# coil_inj_drivers.net
KiCad netlist of a schematic drawn in Altium Designer
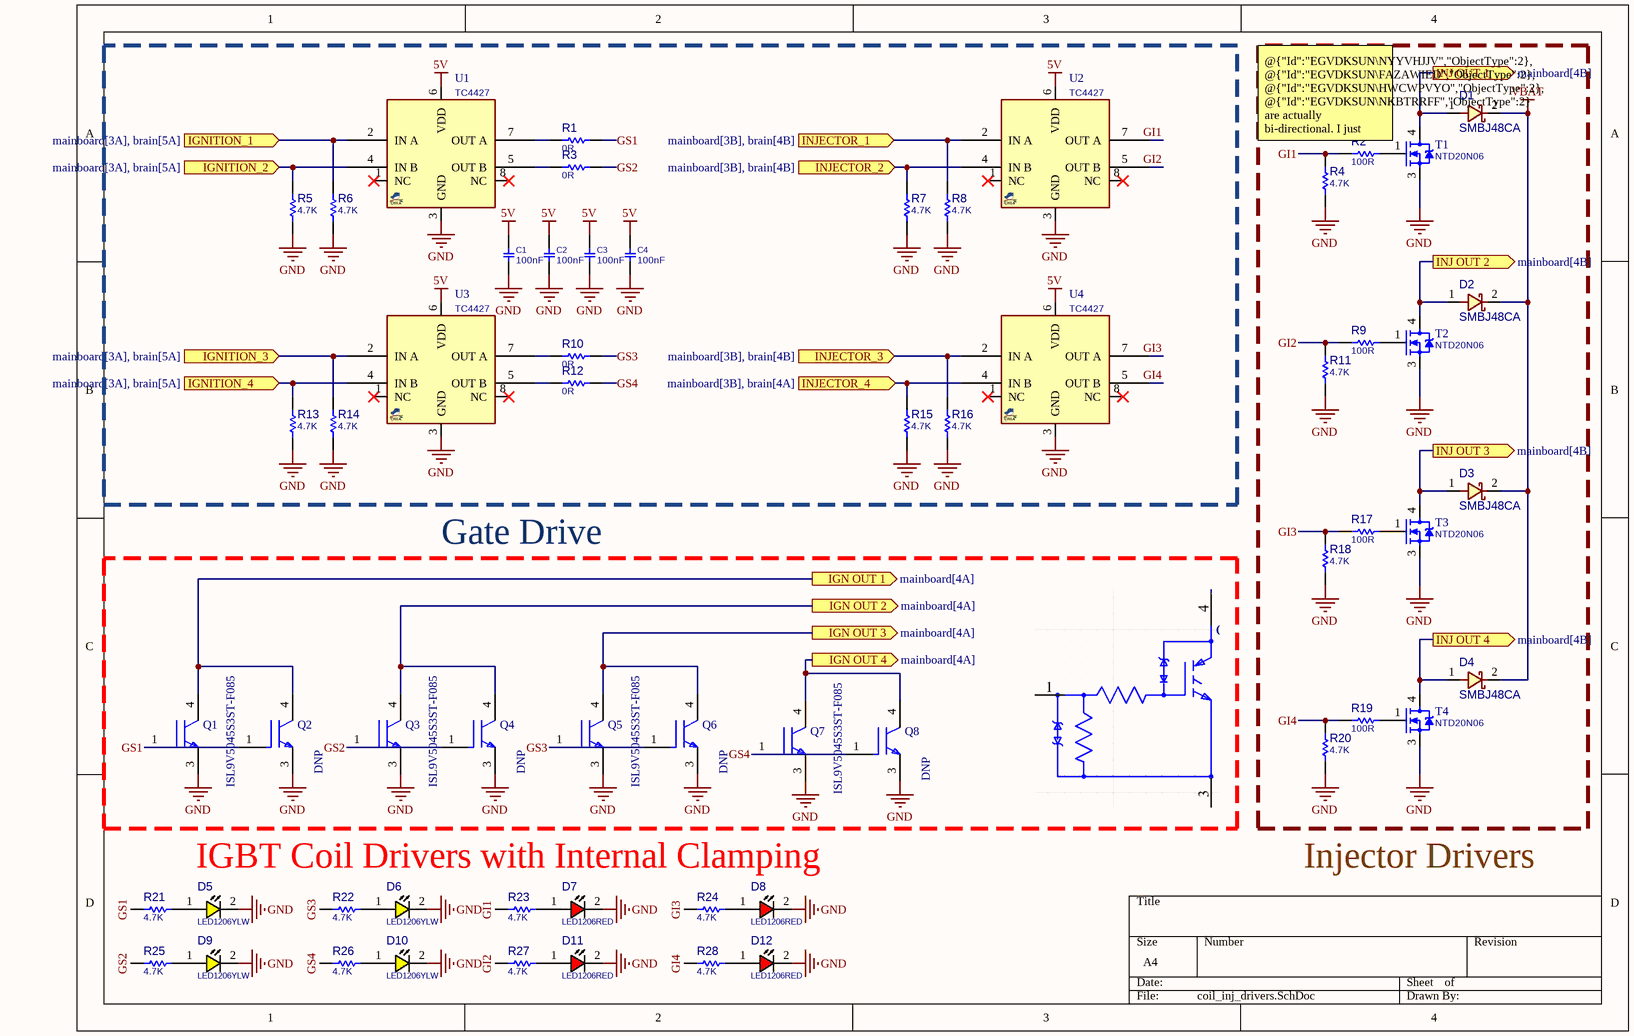
[diagram p0: coil_inj_drivers.SchDoc]

(export (version "E")
  (design (tool "Eeschema 10.0.6"))
  (components
    (comp (ref "C1")
      (value "100nF")
      (footprint "C1206")
      (description "CAP, MLCC")
      (fields (field (name "MANF_P#") "MANF_PART#") (field (name "MANF") "Murata"))
      (libsource (lib "passive_smd") (part "CAP_SMD_MLCC"))
    )
    (comp (ref "C2")
      (value "100nF")
      (footprint "C1206")
      (description "CAP, MLCC")
      (fields (field (name "MANF_P#") "MANF_PART#") (field (name "MANF") "Murata"))
      (libsource (lib "passive_smd") (part "CAP_SMD_MLCC"))
    )
    (comp (ref "C3")
      (value "100nF")
      (footprint "C1206")
      (description "CAP, MLCC")
      (fields (field (name "MANF_P#") "MANF_PART#") (field (name "MANF") "Murata"))
      (libsource (lib "passive_smd") (part "CAP_SMD_MLCC"))
    )
    (comp (ref "C4")
      (value "100nF")
      (footprint "C1206")
      (description "CAP, MLCC")
      (fields (field (name "MANF_P#") "MANF_PART#") (field (name "MANF") "Murata"))
      (libsource (lib "passive_smd") (part "CAP_SMD_MLCC"))
    )
    (comp (ref "D1")
      (value "SMBJ48CA")
      (footprint "D_SMB")
      (description "DIODE, SCHOTTKY, 20V, 3A")
      (fields (field (name "MANF") "VISHAY") (field (name "MANF_P#") "SS34"))
      (libsource (lib "diode") (part "DIODE_SMD_SCHOTTKY_SS34"))
    )
    (comp (ref "D2")
      (value "SMBJ48CA")
      (footprint "D_SMB")
      (description "DIODE, SCHOTTKY, 20V, 3A")
      (fields (field (name "MANF") "VISHAY") (field (name "MANF_P#") "SS34"))
      (libsource (lib "diode") (part "DIODE_SMD_SCHOTTKY_SS34"))
    )
    (comp (ref "D3")
      (value "SMBJ48CA")
      (footprint "D_SMB")
      (description "DIODE, SCHOTTKY, 20V, 3A")
      (fields (field (name "MANF") "VISHAY") (field (name "MANF_P#") "SS34"))
      (libsource (lib "diode") (part "DIODE_SMD_SCHOTTKY_SS34"))
    )
    (comp (ref "D4")
      (value "SMBJ48CA")
      (footprint "D_SMB")
      (description "DIODE, SCHOTTKY, 20V, 3A")
      (fields (field (name "MANF") "VISHAY") (field (name "MANF_P#") "SS34"))
      (libsource (lib "diode") (part "DIODE_SMD_SCHOTTKY_SS34"))
    )
    (comp (ref "D5")
      (value "LED1206YLW")
      (footprint "LED1206YLW")
      (description "LED, SMD, 1206, YELLOW")
      (fields (field (name "MANF") "MANF") (field (name "MANF_P#") "MANF_PART#"))
      (libsource (lib "led(diode)") (part "LED_SMD_1206_YLW"))
    )
    (comp (ref "D6")
      (value "LED1206YLW")
      (footprint "LED1206YLW")
      (description "LED, SMD, 1206, YELLOW")
      (fields (field (name "MANF") "MANF") (field (name "MANF_P#") "MANF_PART#"))
      (libsource (lib "led(diode)") (part "LED_SMD_1206_YLW"))
    )
    (comp (ref "D7")
      (value "LED1206RED")
      (footprint "LED1206RED")
      (description "LED, SMD, 1206, RED")
      (fields (field (name "MANF") "MANF") (field (name "MANF_P#") "MANF_PART#"))
      (libsource (lib "led(diode)") (part "LED_SMD_1206_RED"))
    )
    (comp (ref "D8")
      (value "LED1206RED")
      (footprint "LED1206RED")
      (description "LED, SMD, 1206, RED")
      (fields (field (name "MANF") "MANF") (field (name "MANF_P#") "MANF_PART#"))
      (libsource (lib "led(diode)") (part "LED_SMD_1206_RED"))
    )
    (comp (ref "D9")
      (value "LED1206YLW")
      (footprint "LED1206YLW")
      (description "LED, SMD, 1206, YELLOW")
      (fields (field (name "MANF") "MANF") (field (name "MANF_P#") "MANF_PART#"))
      (libsource (lib "led(diode)") (part "LED_SMD_1206_YLW"))
    )
    (comp (ref "D10")
      (value "LED1206YLW")
      (footprint "LED1206YLW")
      (description "LED, SMD, 1206, YELLOW")
      (fields (field (name "MANF") "MANF") (field (name "MANF_P#") "MANF_PART#"))
      (libsource (lib "led(diode)") (part "LED_SMD_1206_YLW"))
    )
    (comp (ref "D11")
      (value "LED1206RED")
      (footprint "LED1206RED")
      (description "LED, SMD, 1206, RED")
      (fields (field (name "MANF") "MANF") (field (name "MANF_P#") "MANF_PART#"))
      (libsource (lib "led(diode)") (part "LED_SMD_1206_RED"))
    )
    (comp (ref "D12")
      (value "LED1206RED")
      (footprint "LED1206RED")
      (description "LED, SMD, 1206, RED")
      (fields (field (name "MANF") "MANF") (field (name "MANF_P#") "MANF_PART#"))
      (libsource (lib "led(diode)") (part "LED_SMD_1206_RED"))
    )
    (comp (ref "Q1")
      (value "ISL9V5045S3ST-F085")
      (footprint "FP-418AJ-MFG")
      (description "ISL9V5045S3ST-F085 Trans IGBT Chip N-CH 445V 51A 300000mW Automotive 3-Pin(2+Tab) D2PAK T/R")
      (libsource (lib "Altium Content Vault") (part "6c8866ed3e1cdd60f937be2a65c5a66"))
    )
    (comp (ref "Q2")
      (value "DNP")
      (footprint "FP-369AS-MFG")
      (description "IGNITION IGBT")
      (libsource (lib "alib") (part "IGNITION IGBT"))
    )
    (comp (ref "Q3")
      (value "ISL9V5045S3ST-F085")
      (footprint "FP-418AJ-MFG")
      (description "ISL9V5045S3ST-F085 Trans IGBT Chip N-CH 445V 51A 300000mW Automotive 3-Pin(2+Tab) D2PAK T/R")
      (libsource (lib "Altium Content Vault") (part "6c8866ed3e1cdd60f937be2a65c5a66"))
    )
    (comp (ref "Q4")
      (value "DNP")
      (footprint "FP-369AS-MFG")
      (description "IGNITION IGBT")
      (libsource (lib "alib") (part "IGNITION IGBT"))
    )
    (comp (ref "Q5")
      (value "ISL9V5045S3ST-F085")
      (footprint "FP-418AJ-MFG")
      (description "ISL9V5045S3ST-F085 Trans IGBT Chip N-CH 445V 51A 300000mW Automotive 3-Pin(2+Tab) D2PAK T/R")
      (libsource (lib "Altium Content Vault") (part "6c8866ed3e1cdd60f937be2a65c5a66"))
    )
    (comp (ref "Q6")
      (value "DNP")
      (footprint "FP-369AS-MFG")
      (description "IGNITION IGBT")
      (libsource (lib "alib") (part "IGNITION IGBT"))
    )
    (comp (ref "Q7")
      (value "ISL9V5045S3ST-F085")
      (footprint "FP-418AJ-MFG")
      (description "ISL9V5045S3ST-F085 Trans IGBT Chip N-CH 445V 51A 300000mW Automotive 3-Pin(2+Tab) D2PAK T/R")
      (libsource (lib "Altium Content Vault") (part "6c8866ed3e1cdd60f937be2a65c5a66"))
    )
    (comp (ref "Q8")
      (value "DNP")
      (footprint "FP-369AS-MFG")
      (description "IGNITION IGBT")
      (libsource (lib "alib") (part "IGNITION IGBT"))
    )
    (comp (ref "R1")
      (value "0R")
      (footprint "R0805")
      (description "RESISTOR, SMD")
      (libsource (lib "passive_smd") (part "RES_SMD_0805"))
    )
    (comp (ref "R2")
      (value "100R")
      (footprint "R0805")
      (description "RESISTOR, SMD")
      (libsource (lib "passive_smd") (part "RES_SMD_0805"))
    )
    (comp (ref "R3")
      (value "0R")
      (footprint "R0805")
      (description "RESISTOR, SMD")
      (libsource (lib "passive_smd") (part "RES_SMD_0805"))
    )
    (comp (ref "R4")
      (value "4.7K")
      (footprint "R0805")
      (description "RESISTOR, SMD")
      (libsource (lib "passive_smd") (part "RES_SMD_0805"))
    )
    (comp (ref "R5")
      (value "4.7K")
      (footprint "R0805")
      (description "RESISTOR, SMD")
      (libsource (lib "passive_smd") (part "RES_SMD_0805"))
    )
    (comp (ref "R6")
      (value "4.7K")
      (footprint "R0805")
      (description "RESISTOR, SMD")
      (libsource (lib "passive_smd") (part "RES_SMD_0805"))
    )
    (comp (ref "R7")
      (value "4.7K")
      (footprint "R0805")
      (description "RESISTOR, SMD")
      (libsource (lib "passive_smd") (part "RES_SMD_0805"))
    )
    (comp (ref "R8")
      (value "4.7K")
      (footprint "R0805")
      (description "RESISTOR, SMD")
      (libsource (lib "passive_smd") (part "RES_SMD_0805"))
    )
    (comp (ref "R9")
      (value "100R")
      (footprint "R0805")
      (description "RESISTOR, SMD")
      (libsource (lib "passive_smd") (part "RES_SMD_0805"))
    )
    (comp (ref "R10")
      (value "0R")
      (footprint "R0805")
      (description "RESISTOR, SMD")
      (libsource (lib "passive_smd") (part "RES_SMD_0805"))
    )
    (comp (ref "R11")
      (value "4.7K")
      (footprint "R0805")
      (description "RESISTOR, SMD")
      (libsource (lib "passive_smd") (part "RES_SMD_0805"))
    )
    (comp (ref "R12")
      (value "0R")
      (footprint "R0805")
      (description "RESISTOR, SMD")
      (libsource (lib "passive_smd") (part "RES_SMD_0805"))
    )
    (comp (ref "R13")
      (value "4.7K")
      (footprint "R0805")
      (description "RESISTOR, SMD")
      (libsource (lib "passive_smd") (part "RES_SMD_0805"))
    )
    (comp (ref "R14")
      (value "4.7K")
      (footprint "R0805")
      (description "RESISTOR, SMD")
      (libsource (lib "passive_smd") (part "RES_SMD_0805"))
    )
    (comp (ref "R15")
      (value "4.7K")
      (footprint "R0805")
      (description "RESISTOR, SMD")
      (libsource (lib "passive_smd") (part "RES_SMD_0805"))
    )
    (comp (ref "R16")
      (value "4.7K")
      (footprint "R0805")
      (description "RESISTOR, SMD")
      (libsource (lib "passive_smd") (part "RES_SMD_0805"))
    )
    (comp (ref "R17")
      (value "100R")
      (footprint "R0805")
      (description "RESISTOR, SMD")
      (libsource (lib "passive_smd") (part "RES_SMD_0805"))
    )
    (comp (ref "R18")
      (value "4.7K")
      (footprint "R0805")
      (description "RESISTOR, SMD")
      (libsource (lib "passive_smd") (part "RES_SMD_0805"))
    )
    (comp (ref "R19")
      (value "100R")
      (footprint "R0805")
      (description "RESISTOR, SMD")
      (libsource (lib "passive_smd") (part "RES_SMD_0805"))
    )
    (comp (ref "R20")
      (value "4.7K")
      (footprint "R0805")
      (description "RESISTOR, SMD")
      (libsource (lib "passive_smd") (part "RES_SMD_0805"))
    )
    (comp (ref "R21")
      (value "4.7K")
      (footprint "R0805")
      (description "RESISTOR, SMD")
      (libsource (lib "passive_smd") (part "RES_SMD_0805"))
    )
    (comp (ref "R22")
      (value "4.7K")
      (footprint "R0805")
      (description "RESISTOR, SMD")
      (libsource (lib "passive_smd") (part "RES_SMD_0805"))
    )
    (comp (ref "R23")
      (value "4.7K")
      (footprint "R0805")
      (description "RESISTOR, SMD")
      (libsource (lib "passive_smd") (part "RES_SMD_0805"))
    )
    (comp (ref "R24")
      (value "4.7K")
      (footprint "R0805")
      (description "RESISTOR, SMD")
      (libsource (lib "passive_smd") (part "RES_SMD_0805"))
    )
    (comp (ref "R25")
      (value "4.7K")
      (footprint "R0805")
      (description "RESISTOR, SMD")
      (libsource (lib "passive_smd") (part "RES_SMD_0805"))
    )
    (comp (ref "R26")
      (value "4.7K")
      (footprint "R0805")
      (description "RESISTOR, SMD")
      (libsource (lib "passive_smd") (part "RES_SMD_0805"))
    )
    (comp (ref "R27")
      (value "4.7K")
      (footprint "R0805")
      (description "RESISTOR, SMD")
      (libsource (lib "passive_smd") (part "RES_SMD_0805"))
    )
    (comp (ref "R28")
      (value "4.7K")
      (footprint "R0805")
      (description "RESISTOR, SMD")
      (libsource (lib "passive_smd") (part "RES_SMD_0805"))
    )
    (comp (ref "T1")
      (value "NTD20N06")
      (footprint "DPAK_3")
      (description "MOSFET, N-CH, 60V, 20A, 39mRDS, 1~2VGSth")
      (fields (field (name "MANF_P#") "NTD20N06L") (field (name "MANF") "ON"))
      (libsource (lib "transistor_fet") (part "MOSN_NTD20N06_DPAK"))
    )
    (comp (ref "T2")
      (value "NTD20N06")
      (footprint "DPAK_3")
      (description "MOSFET, N-CH, 60V, 20A, 39mRDS, 1~2VGSth")
      (fields (field (name "MANF_P#") "NTD20N06L") (field (name "MANF") "ON"))
      (libsource (lib "transistor_fet") (part "MOSN_NTD20N06_DPAK"))
    )
    (comp (ref "T3")
      (value "NTD20N06")
      (footprint "DPAK_3")
      (description "MOSFET, N-CH, 60V, 20A, 39mRDS, 1~2VGSth")
      (fields (field (name "MANF_P#") "NTD20N06L") (field (name "MANF") "ON"))
      (libsource (lib "transistor_fet") (part "MOSN_NTD20N06_DPAK"))
    )
    (comp (ref "T4")
      (value "NTD20N06")
      (footprint "DPAK_3")
      (description "MOSFET, N-CH, 60V, 20A, 39mRDS, 1~2VGSth")
      (fields (field (name "MANF_P#") "NTD20N06L") (field (name "MANF") "ON"))
      (libsource (lib "transistor_fet") (part "MOSN_NTD20N06_DPAK"))
    )
    (comp (ref "U1")
      (value "TC4427")
      (footprint "SO_8")
      (description "power Mosfet Driver, Dual, High-Speed, 1.5A")
      (libsource (lib "transistor_fet") (part "MOS_DUAL_TC4427"))
    )
    (comp (ref "U2")
      (value "TC4427")
      (footprint "SO_8")
      (description "power Mosfet Driver, Dual, High-Speed, 1.5A")
      (libsource (lib "transistor_fet") (part "MOS_DUAL_TC4427"))
    )
    (comp (ref "U3")
      (value "TC4427")
      (footprint "SO_8")
      (description "power Mosfet Driver, Dual, High-Speed, 1.5A")
      (libsource (lib "transistor_fet") (part "MOS_DUAL_TC4427"))
    )
    (comp (ref "U4")
      (value "TC4427")
      (footprint "SO_8")
      (description "power Mosfet Driver, Dual, High-Speed, 1.5A")
      (libsource (lib "transistor_fet") (part "MOS_DUAL_TC4427"))
    )
  )
  (nets
    (net (code "1") (name "/GI1") (class "Default")
      (node (ref "R2") (pin "2") (pinfunction "2_2") (pintype "passive"))
      (node (ref "R23") (pin "2") (pinfunction "2_2") (pintype "passive"))
      (node (ref "R4") (pin "2") (pinfunction "2_2") (pintype "passive"))
      (node (ref "U2") (pin "7") (pinfunction "OUT_A_7") (pintype "passive"))
    )
    (net (code "2") (name "/GI2") (class "Default")
      (node (ref "R11") (pin "2") (pinfunction "2_2") (pintype "passive"))
      (node (ref "R27") (pin "2") (pinfunction "2_2") (pintype "passive"))
      (node (ref "R9") (pin "2") (pinfunction "2_2") (pintype "passive"))
      (node (ref "U2") (pin "5") (pinfunction "OUT_B_5") (pintype "passive"))
    )
    (net (code "3") (name "/GI3") (class "Default")
      (node (ref "R17") (pin "2") (pinfunction "2_2") (pintype "passive"))
      (node (ref "R18") (pin "2") (pinfunction "2_2") (pintype "passive"))
      (node (ref "R24") (pin "2") (pinfunction "2_2") (pintype "passive"))
      (node (ref "U4") (pin "7") (pinfunction "OUT_A_7") (pintype "passive"))
    )
    (net (code "4") (name "/GI4") (class "Default")
      (node (ref "R19") (pin "2") (pinfunction "2_2") (pintype "passive"))
      (node (ref "R20") (pin "2") (pinfunction "2_2") (pintype "passive"))
      (node (ref "R28") (pin "2") (pinfunction "2_2") (pintype "passive"))
      (node (ref "U4") (pin "5") (pinfunction "OUT_B_5") (pintype "passive"))
    )
    (net (code "5") (name "/GS1") (class "Default")
      (node (ref "Q1") (pin "1") (pinfunction "GATE_1") (pintype "passive"))
      (node (ref "Q2") (pin "1") (pinfunction "GATE_1") (pintype "passive"))
      (node (ref "R1") (pin "1") (pinfunction "1_1") (pintype "passive"))
      (node (ref "R21") (pin "2") (pinfunction "2_2") (pintype "passive"))
    )
    (net (code "6") (name "/GS2") (class "Default")
      (node (ref "Q3") (pin "1") (pinfunction "GATE_1") (pintype "passive"))
      (node (ref "Q4") (pin "1") (pinfunction "GATE_1") (pintype "passive"))
      (node (ref "R25") (pin "2") (pinfunction "2_2") (pintype "passive"))
      (node (ref "R3") (pin "1") (pinfunction "1_1") (pintype "passive"))
    )
    (net (code "7") (name "/GS3") (class "Default")
      (node (ref "Q5") (pin "1") (pinfunction "GATE_1") (pintype "passive"))
      (node (ref "Q6") (pin "1") (pinfunction "GATE_1") (pintype "passive"))
      (node (ref "R10") (pin "1") (pinfunction "1_1") (pintype "passive"))
      (node (ref "R22") (pin "2") (pinfunction "2_2") (pintype "passive"))
    )
    (net (code "8") (name "/GS4") (class "Default")
      (node (ref "Q7") (pin "1") (pinfunction "GATE_1") (pintype "passive"))
      (node (ref "Q8") (pin "1") (pinfunction "GATE_1") (pintype "passive"))
      (node (ref "R12") (pin "1") (pinfunction "1_1") (pintype "passive"))
      (node (ref "R26") (pin "2") (pinfunction "2_2") (pintype "passive"))
    )
    (net (code "9") (name "/IGN OUT 1") (class "Default")
      (node (ref "Q1") (pin "4") (pinfunction "C_4") (pintype "passive"))
      (node (ref "Q2") (pin "4") (pinfunction "C_4") (pintype "passive"))
    )
    (net (code "10") (name "/IGN OUT 2") (class "Default")
      (node (ref "Q3") (pin "4") (pinfunction "C_4") (pintype "passive"))
      (node (ref "Q4") (pin "4") (pinfunction "C_4") (pintype "passive"))
    )
    (net (code "11") (name "/IGN OUT 3") (class "Default")
      (node (ref "Q5") (pin "4") (pinfunction "C_4") (pintype "passive"))
      (node (ref "Q6") (pin "4") (pinfunction "C_4") (pintype "passive"))
    )
    (net (code "12") (name "/IGN OUT 4") (class "Default")
      (node (ref "Q7") (pin "4") (pinfunction "C_4") (pintype "passive"))
      (node (ref "Q8") (pin "4") (pinfunction "C_4") (pintype "passive"))
    )
    (net (code "13") (name "/IGNITION_1") (class "Default")
      (node (ref "R6") (pin "2") (pinfunction "2_2") (pintype "passive"))
      (node (ref "U1") (pin "2") (pinfunction "IN_A_2") (pintype "passive"))
    )
    (net (code "14") (name "/IGNITION_2") (class "Default")
      (node (ref "R5") (pin "2") (pinfunction "2_2") (pintype "passive"))
      (node (ref "U1") (pin "4") (pinfunction "IN_B_4") (pintype "passive"))
    )
    (net (code "15") (name "/IGNITION_3") (class "Default")
      (node (ref "R14") (pin "2") (pinfunction "2_2") (pintype "passive"))
      (node (ref "U3") (pin "2") (pinfunction "IN_A_2") (pintype "passive"))
    )
    (net (code "16") (name "/IGNITION_4") (class "Default")
      (node (ref "R13") (pin "2") (pinfunction "2_2") (pintype "passive"))
      (node (ref "U3") (pin "4") (pinfunction "IN_B_4") (pintype "passive"))
    )
    (net (code "17") (name "/INJ OUT 1") (class "Default")
      (node (ref "D1") (pin "1") (pinfunction "1_1") (pintype "passive"))
      (node (ref "T1") (pin "4") (pinfunction "D_4") (pintype "passive"))
    )
    (net (code "18") (name "/INJ OUT 2") (class "Default")
      (node (ref "D2") (pin "1") (pinfunction "1_1") (pintype "passive"))
      (node (ref "T2") (pin "4") (pinfunction "D_4") (pintype "passive"))
    )
    (net (code "19") (name "/INJ OUT 3") (class "Default")
      (node (ref "D3") (pin "1") (pinfunction "1_1") (pintype "passive"))
      (node (ref "T3") (pin "4") (pinfunction "D_4") (pintype "passive"))
    )
    (net (code "20") (name "/INJ OUT 4") (class "Default")
      (node (ref "D4") (pin "1") (pinfunction "1_1") (pintype "passive"))
      (node (ref "T4") (pin "4") (pinfunction "D_4") (pintype "passive"))
    )
    (net (code "21") (name "/INJECTOR_1") (class "Default")
      (node (ref "R8") (pin "2") (pinfunction "2_2") (pintype "passive"))
      (node (ref "U2") (pin "2") (pinfunction "IN_A_2") (pintype "passive"))
    )
    (net (code "22") (name "/INJECTOR_2") (class "Default")
      (node (ref "R7") (pin "2") (pinfunction "2_2") (pintype "passive"))
      (node (ref "U2") (pin "4") (pinfunction "IN_B_4") (pintype "passive"))
    )
    (net (code "23") (name "/INJECTOR_3") (class "Default")
      (node (ref "R16") (pin "2") (pinfunction "2_2") (pintype "passive"))
      (node (ref "U4") (pin "2") (pinfunction "IN_A_2") (pintype "passive"))
    )
    (net (code "24") (name "/INJECTOR_4") (class "Default")
      (node (ref "R15") (pin "2") (pinfunction "2_2") (pintype "passive"))
      (node (ref "U4") (pin "4") (pinfunction "IN_B_4") (pintype "passive"))
    )
    (net (code "25") (name "5V") (class "Default")
      (node (ref "C1") (pin "2") (pinfunction "2_2") (pintype "passive"))
      (node (ref "C2") (pin "2") (pinfunction "2_2") (pintype "passive"))
      (node (ref "C3") (pin "2") (pinfunction "2_2") (pintype "passive"))
      (node (ref "C4") (pin "2") (pinfunction "2_2") (pintype "passive"))
      (node (ref "U1") (pin "6") (pinfunction "VDD_6") (pintype "passive"))
      (node (ref "U2") (pin "6") (pinfunction "VDD_6") (pintype "passive"))
      (node (ref "U3") (pin "6") (pinfunction "VDD_6") (pintype "passive"))
      (node (ref "U4") (pin "6") (pinfunction "VDD_6") (pintype "passive"))
    )
    (net (code "26") (name "GND") (class "Default")
      (node (ref "C1") (pin "1") (pinfunction "1_1") (pintype "passive"))
      (node (ref "C2") (pin "1") (pinfunction "1_1") (pintype "passive"))
      (node (ref "C3") (pin "1") (pinfunction "1_1") (pintype "passive"))
      (node (ref "C4") (pin "1") (pinfunction "1_1") (pintype "passive"))
      (node (ref "D10") (pin "2") (pinfunction "CATHODE_2") (pintype "passive"))
      (node (ref "D11") (pin "2") (pinfunction "CATHODE_2") (pintype "passive"))
      (node (ref "D12") (pin "2") (pinfunction "CATHODE_2") (pintype "passive"))
      (node (ref "D5") (pin "2") (pinfunction "CATHODE_2") (pintype "passive"))
      (node (ref "D6") (pin "2") (pinfunction "CATHODE_2") (pintype "passive"))
      (node (ref "D7") (pin "2") (pinfunction "CATHODE_2") (pintype "passive"))
      (node (ref "D8") (pin "2") (pinfunction "CATHODE_2") (pintype "passive"))
      (node (ref "D9") (pin "2") (pinfunction "CATHODE_2") (pintype "passive"))
      (node (ref "Q1") (pin "3") (pinfunction "E_3") (pintype "passive"))
      (node (ref "Q2") (pin "3") (pinfunction "E_3") (pintype "passive"))
      (node (ref "Q3") (pin "3") (pinfunction "E_3") (pintype "passive"))
      (node (ref "Q4") (pin "3") (pinfunction "E_3") (pintype "passive"))
      (node (ref "Q5") (pin "3") (pinfunction "E_3") (pintype "passive"))
      (node (ref "Q6") (pin "3") (pinfunction "E_3") (pintype "passive"))
      (node (ref "Q7") (pin "3") (pinfunction "E_3") (pintype "passive"))
      (node (ref "Q8") (pin "3") (pinfunction "E_3") (pintype "passive"))
      (node (ref "R11") (pin "1") (pinfunction "1_1") (pintype "passive"))
      (node (ref "R13") (pin "1") (pinfunction "1_1") (pintype "passive"))
      (node (ref "R14") (pin "1") (pinfunction "1_1") (pintype "passive"))
      (node (ref "R15") (pin "1") (pinfunction "1_1") (pintype "passive"))
      (node (ref "R16") (pin "1") (pinfunction "1_1") (pintype "passive"))
      (node (ref "R18") (pin "1") (pinfunction "1_1") (pintype "passive"))
      (node (ref "R20") (pin "1") (pinfunction "1_1") (pintype "passive"))
      (node (ref "R4") (pin "1") (pinfunction "1_1") (pintype "passive"))
      (node (ref "R5") (pin "1") (pinfunction "1_1") (pintype "passive"))
      (node (ref "R6") (pin "1") (pinfunction "1_1") (pintype "passive"))
      (node (ref "R7") (pin "1") (pinfunction "1_1") (pintype "passive"))
      (node (ref "R8") (pin "1") (pinfunction "1_1") (pintype "passive"))
      (node (ref "T1") (pin "3") (pinfunction "S_3") (pintype "passive"))
      (node (ref "T2") (pin "3") (pinfunction "S_3") (pintype "passive"))
      (node (ref "T3") (pin "3") (pinfunction "S_3") (pintype "passive"))
      (node (ref "T4") (pin "3") (pinfunction "S_3") (pintype "passive"))
      (node (ref "U1") (pin "3") (pinfunction "GND_3") (pintype "passive"))
      (node (ref "U2") (pin "3") (pinfunction "GND_3") (pintype "passive"))
      (node (ref "U3") (pin "3") (pinfunction "GND_3") (pintype "passive"))
      (node (ref "U4") (pin "3") (pinfunction "GND_3") (pintype "passive"))
    )
    (net (code "27") (name "Net-(D5-ANODE)") (class "Default")
      (node (ref "D5") (pin "1") (pinfunction "ANODE_1") (pintype "passive"))
      (node (ref "R21") (pin "1") (pinfunction "1_1") (pintype "passive"))
    )
    (net (code "28") (name "Net-(D6-ANODE)") (class "Default")
      (node (ref "D6") (pin "1") (pinfunction "ANODE_1") (pintype "passive"))
      (node (ref "R22") (pin "1") (pinfunction "1_1") (pintype "passive"))
    )
    (net (code "29") (name "Net-(D7-ANODE)") (class "Default")
      (node (ref "D7") (pin "1") (pinfunction "ANODE_1") (pintype "passive"))
      (node (ref "R23") (pin "1") (pinfunction "1_1") (pintype "passive"))
    )
    (net (code "30") (name "Net-(D8-ANODE)") (class "Default")
      (node (ref "D8") (pin "1") (pinfunction "ANODE_1") (pintype "passive"))
      (node (ref "R24") (pin "1") (pinfunction "1_1") (pintype "passive"))
    )
    (net (code "31") (name "Net-(D9-ANODE)") (class "Default")
      (node (ref "D9") (pin "1") (pinfunction "ANODE_1") (pintype "passive"))
      (node (ref "R25") (pin "1") (pinfunction "1_1") (pintype "passive"))
    )
    (net (code "32") (name "Net-(D10-ANODE)") (class "Default")
      (node (ref "D10") (pin "1") (pinfunction "ANODE_1") (pintype "passive"))
      (node (ref "R26") (pin "1") (pinfunction "1_1") (pintype "passive"))
    )
    (net (code "33") (name "Net-(D11-ANODE)") (class "Default")
      (node (ref "D11") (pin "1") (pinfunction "ANODE_1") (pintype "passive"))
      (node (ref "R27") (pin "1") (pinfunction "1_1") (pintype "passive"))
    )
    (net (code "34") (name "Net-(D12-ANODE)") (class "Default")
      (node (ref "D12") (pin "1") (pinfunction "ANODE_1") (pintype "passive"))
      (node (ref "R28") (pin "1") (pinfunction "1_1") (pintype "passive"))
    )
    (net (code "35") (name "Net-(T1-G)") (class "Default")
      (node (ref "R2") (pin "1") (pinfunction "1_1") (pintype "passive"))
      (node (ref "T1") (pin "1") (pinfunction "G_1") (pintype "passive"))
    )
    (net (code "36") (name "Net-(T2-G)") (class "Default")
      (node (ref "R9") (pin "1") (pinfunction "1_1") (pintype "passive"))
      (node (ref "T2") (pin "1") (pinfunction "G_1") (pintype "passive"))
    )
    (net (code "37") (name "Net-(T3-G)") (class "Default")
      (node (ref "R17") (pin "1") (pinfunction "1_1") (pintype "passive"))
      (node (ref "T3") (pin "1") (pinfunction "G_1") (pintype "passive"))
    )
    (net (code "38") (name "Net-(T4-G)") (class "Default")
      (node (ref "R19") (pin "1") (pinfunction "1_1") (pintype "passive"))
      (node (ref "T4") (pin "1") (pinfunction "G_1") (pintype "passive"))
    )
    (net (code "39") (name "Net-(U1-OUT_A)") (class "Default")
      (node (ref "R1") (pin "2") (pinfunction "2_2") (pintype "passive"))
      (node (ref "U1") (pin "7") (pinfunction "OUT_A_7") (pintype "passive"))
    )
    (net (code "40") (name "Net-(U1-OUT_B)") (class "Default")
      (node (ref "R3") (pin "2") (pinfunction "2_2") (pintype "passive"))
      (node (ref "U1") (pin "5") (pinfunction "OUT_B_5") (pintype "passive"))
    )
    (net (code "41") (name "Net-(U3-OUT_A)") (class "Default")
      (node (ref "R10") (pin "2") (pinfunction "2_2") (pintype "passive"))
      (node (ref "U3") (pin "7") (pinfunction "OUT_A_7") (pintype "passive"))
    )
    (net (code "42") (name "Net-(U3-OUT_B)") (class "Default")
      (node (ref "R12") (pin "2") (pinfunction "2_2") (pintype "passive"))
      (node (ref "U3") (pin "5") (pinfunction "OUT_B_5") (pintype "passive"))
    )
    (net (code "43") (name "VBAT") (class "Default")
      (node (ref "D1") (pin "2") (pinfunction "2_2") (pintype "passive"))
      (node (ref "D2") (pin "2") (pinfunction "2_2") (pintype "passive"))
      (node (ref "D3") (pin "2") (pinfunction "2_2") (pintype "passive"))
      (node (ref "D4") (pin "2") (pinfunction "2_2") (pintype "passive"))
    )
    (net (code "44") (name "unconnected-(U1-NC-Pad1)") (class "Default")
      (node (ref "U1") (pin "1") (pinfunction "NC_1") (pintype "passive+no_connect"))
    )
    (net (code "45") (name "unconnected-(U1-NC-Pad8)") (class "Default")
      (node (ref "U1") (pin "8") (pinfunction "NC_8") (pintype "passive+no_connect"))
    )
    (net (code "46") (name "unconnected-(U2-NC-Pad1)") (class "Default")
      (node (ref "U2") (pin "1") (pinfunction "NC_1") (pintype "passive+no_connect"))
    )
    (net (code "47") (name "unconnected-(U2-NC-Pad8)") (class "Default")
      (node (ref "U2") (pin "8") (pinfunction "NC_8") (pintype "passive+no_connect"))
    )
    (net (code "48") (name "unconnected-(U3-NC-Pad1)") (class "Default")
      (node (ref "U3") (pin "1") (pinfunction "NC_1") (pintype "passive+no_connect"))
    )
    (net (code "49") (name "unconnected-(U3-NC-Pad8)") (class "Default")
      (node (ref "U3") (pin "8") (pinfunction "NC_8") (pintype "passive+no_connect"))
    )
    (net (code "50") (name "unconnected-(U4-NC-Pad1)") (class "Default")
      (node (ref "U4") (pin "1") (pinfunction "NC_1") (pintype "passive+no_connect"))
    )
    (net (code "51") (name "unconnected-(U4-NC-Pad8)") (class "Default")
      (node (ref "U4") (pin "8") (pinfunction "NC_8") (pintype "passive+no_connect"))
    )
  )
)
